# sensor_interface.net
KiCad netlist of a schematic drawn in EAGLE
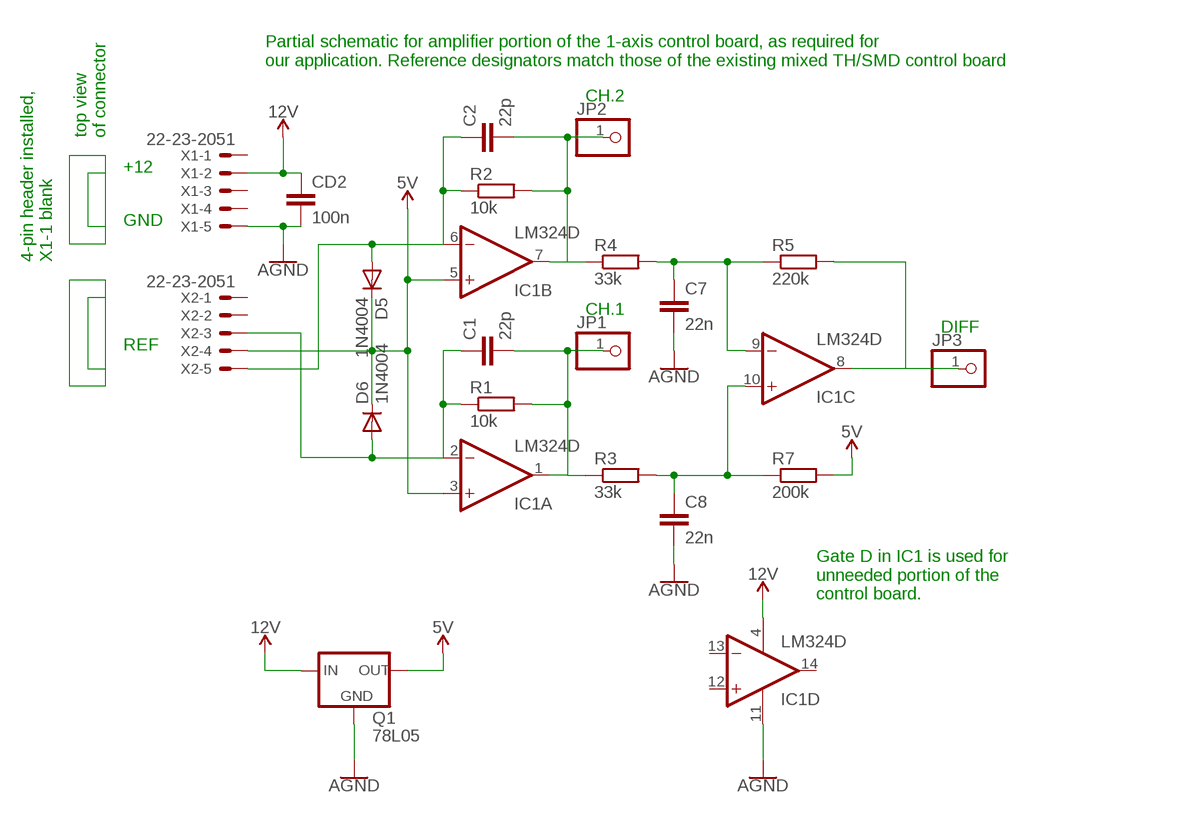
[diagram p0: schematic, sheet 1]

(export (version "E")
  (design (tool "Eeschema 10.0.6"))
  (components
    (comp (ref "C1")
      (value "22p")
      (footprint "eagle-import:C025-024X044")
      (libsource (lib "eagle-import") (part "C-EU025-024X044"))
    )
    (comp (ref "C2")
      (value "22p")
      (footprint "eagle-import:C025-024X044")
      (libsource (lib "eagle-import") (part "C-EU025-024X044"))
    )
    (comp (ref "C7")
      (value "22n")
      (footprint "eagle-import:C025-024X044")
      (libsource (lib "eagle-import") (part "C-EU025-024X044"))
    )
    (comp (ref "C8")
      (value "22n")
      (footprint "eagle-import:C025-024X044")
      (libsource (lib "eagle-import") (part "C-EU025-024X044"))
    )
    (comp (ref "CD2")
      (value "100n")
      (footprint "eagle-import:C025-024X044")
      (libsource (lib "eagle-import") (part "C-EU025-024X044"))
    )
    (comp (ref "D5")
      (value "1N4004")
      (footprint "eagle-import:DO41-10")
      (libsource (lib "eagle-import") (part "1N4004"))
    )
    (comp (ref "D6")
      (value "1N4004")
      (footprint "eagle-import:DO41-10")
      (libsource (lib "eagle-import") (part "1N4004"))
    )
    (comp (ref "IC1")
      (value "LM324D")
      (footprint "eagle-import:SO14")
      (libsource (lib "eagle-import") (part "LM324D"))
    )
    (comp (ref "JP1")
      (value "PINHD-1X1")
      (footprint "eagle-import:1X01")
      (libsource (lib "eagle-import") (part "PINHD-1X1"))
    )
    (comp (ref "JP2")
      (value "PINHD-1X1")
      (footprint "eagle-import:1X01")
      (libsource (lib "eagle-import") (part "PINHD-1X1"))
    )
    (comp (ref "JP3")
      (value "PINHD-1X1")
      (footprint "eagle-import:1X01")
      (libsource (lib "eagle-import") (part "PINHD-1X1"))
    )
    (comp (ref "Q1")
      (value "78L05")
      (footprint "eagle-import:78LXX")
      (libsource (lib "eagle-import") (part "78LXX"))
    )
    (comp (ref "R1")
      (value "10k")
      (footprint "eagle-import:R0805")
      (libsource (lib "eagle-import") (part "R-EU_R0805"))
    )
    (comp (ref "R2")
      (value "10k")
      (footprint "eagle-import:R0805")
      (libsource (lib "eagle-import") (part "R-EU_R0805"))
    )
    (comp (ref "R3")
      (value "33k")
      (footprint "eagle-import:R0805")
      (libsource (lib "eagle-import") (part "R-EU_R0805"))
    )
    (comp (ref "R4")
      (value "33k")
      (footprint "eagle-import:R0805")
      (libsource (lib "eagle-import") (part "R-EU_R0805"))
    )
    (comp (ref "R5")
      (value "220k")
      (footprint "eagle-import:R0805")
      (libsource (lib "eagle-import") (part "R-EU_R0805"))
    )
    (comp (ref "R7")
      (value "200k")
      (footprint "eagle-import:R0805")
      (libsource (lib "eagle-import") (part "R-EU_R0805"))
    )
    (comp (ref "X1")
      (value "22-23-2051")
      (footprint "eagle-import:22-23-2051")
      (fields (field (name "MF") "MOLEX"))
      (libsource (lib "eagle-import") (part "22-23-2051"))
    )
    (comp (ref "X2")
      (value "22-23-2051")
      (footprint "eagle-import:22-23-2051")
      (fields (field (name "MF") "MOLEX"))
      (libsource (lib "eagle-import") (part "22-23-2051"))
    )
  )
  (nets
    (net (code "1") (name "5V") (class "Default")
      (node (ref "D5") (pin "C") (pinfunction "C_C") (pintype "passive"))
      (node (ref "D6") (pin "C") (pinfunction "C_C") (pintype "passive"))
      (node (ref "IC1") (pin "3") (pinfunction "+IN_3") (pintype "input"))
      (node (ref "IC1") (pin "5") (pinfunction "+IN_5") (pintype "input"))
      (node (ref "Q1") (pin "OUT") (pinfunction "OUT_OUT") (pintype "passive"))
      (node (ref "R7") (pin "2") (pinfunction "2_2") (pintype "passive"))
      (node (ref "X2") (pin "4") (pinfunction "S_4") (pintype "passive"))
    )
    (net (code "2") (name "12V") (class "Default")
      (node (ref "CD2") (pin "1") (pinfunction "1_1") (pintype "passive"))
      (node (ref "IC1") (pin "4") (pinfunction "V+_4") (pintype "power_in"))
      (node (ref "Q1") (pin "IN") (pinfunction "IN_IN") (pintype "input"))
      (node (ref "X1") (pin "2") (pinfunction "S_2") (pintype "passive"))
    )
    (net (code "3") (name "AGND") (class "Default")
      (node (ref "C7") (pin "2") (pinfunction "2_2") (pintype "passive"))
      (node (ref "C8") (pin "2") (pinfunction "2_2") (pintype "passive"))
      (node (ref "CD2") (pin "2") (pinfunction "2_2") (pintype "passive"))
      (node (ref "IC1") (pin "11") (pinfunction "V-_11") (pintype "power_in"))
      (node (ref "Q1") (pin "GND") (pinfunction "GND_GND") (pintype "input"))
      (node (ref "X1") (pin "5") (pinfunction "S_5") (pintype "passive"))
    )
    (net (code "4") (name "Net-(IC1A--IN)") (class "Default")
      (node (ref "C1") (pin "1") (pinfunction "1_1") (pintype "passive"))
      (node (ref "D6") (pin "A") (pinfunction "A_A") (pintype "passive"))
      (node (ref "IC1") (pin "2") (pinfunction "-IN_2") (pintype "input"))
      (node (ref "R1") (pin "1") (pinfunction "1_1") (pintype "passive"))
      (node (ref "X2") (pin "3") (pinfunction "S_3") (pintype "passive"))
    )
    (net (code "5") (name "Net-(IC1A-OUT)") (class "Default")
      (node (ref "C1") (pin "2") (pinfunction "2_2") (pintype "passive"))
      (node (ref "IC1") (pin "1") (pinfunction "OUT_1") (pintype "output"))
      (node (ref "JP1") (pin "1") (pinfunction "1_1") (pintype "passive"))
      (node (ref "R1") (pin "2") (pinfunction "2_2") (pintype "passive"))
      (node (ref "R3") (pin "1") (pinfunction "1_1") (pintype "passive"))
    )
    (net (code "6") (name "Net-(IC1B--IN)") (class "Default")
      (node (ref "C2") (pin "1") (pinfunction "1_1") (pintype "passive"))
      (node (ref "D5") (pin "A") (pinfunction "A_A") (pintype "passive"))
      (node (ref "IC1") (pin "6") (pinfunction "-IN_6") (pintype "input"))
      (node (ref "R2") (pin "1") (pinfunction "1_1") (pintype "passive"))
      (node (ref "X2") (pin "5") (pinfunction "S_5") (pintype "passive"))
    )
    (net (code "7") (name "Net-(IC1B-OUT)") (class "Default")
      (node (ref "C2") (pin "2") (pinfunction "2_2") (pintype "passive"))
      (node (ref "IC1") (pin "7") (pinfunction "OUT_7") (pintype "output"))
      (node (ref "JP2") (pin "1") (pinfunction "1_1") (pintype "passive"))
      (node (ref "R2") (pin "2") (pinfunction "2_2") (pintype "passive"))
      (node (ref "R4") (pin "1") (pinfunction "1_1") (pintype "passive"))
    )
    (net (code "8") (name "Net-(IC1C-+IN)") (class "Default")
      (node (ref "C8") (pin "1") (pinfunction "1_1") (pintype "passive"))
      (node (ref "IC1") (pin "10") (pinfunction "+IN_10") (pintype "input"))
      (node (ref "R3") (pin "2") (pinfunction "2_2") (pintype "passive"))
      (node (ref "R7") (pin "1") (pinfunction "1_1") (pintype "passive"))
    )
    (net (code "9") (name "Net-(IC1C--IN)") (class "Default")
      (node (ref "C7") (pin "1") (pinfunction "1_1") (pintype "passive"))
      (node (ref "IC1") (pin "9") (pinfunction "-IN_9") (pintype "input"))
      (node (ref "R4") (pin "2") (pinfunction "2_2") (pintype "passive"))
      (node (ref "R5") (pin "1") (pinfunction "1_1") (pintype "passive"))
    )
    (net (code "10") (name "Net-(IC1C-OUT)") (class "Default")
      (node (ref "IC1") (pin "8") (pinfunction "OUT_8") (pintype "output"))
      (node (ref "JP3") (pin "1") (pinfunction "1_1") (pintype "passive"))
      (node (ref "R5") (pin "2") (pinfunction "2_2") (pintype "passive"))
    )
    (net (code "11") (name "unconnected-(IC1D-+IN-Pad12)") (class "Default")
      (node (ref "IC1") (pin "12") (pinfunction "+IN_12") (pintype "input"))
    )
    (net (code "12") (name "unconnected-(IC1D--IN-Pad13)") (class "Default")
      (node (ref "IC1") (pin "13") (pinfunction "-IN_13") (pintype "input"))
    )
    (net (code "13") (name "unconnected-(IC1D-OUT-Pad14)") (class "Default")
      (node (ref "IC1") (pin "14") (pinfunction "OUT_14") (pintype "output"))
    )
    (net (code "14") (name "unconnected-(X1A-S-Pad1)") (class "Default")
      (node (ref "X1") (pin "1") (pinfunction "S_1") (pintype "passive"))
    )
    (net (code "15") (name "unconnected-(X1C-S-Pad3)") (class "Default")
      (node (ref "X1") (pin "3") (pinfunction "S_3") (pintype "passive"))
    )
    (net (code "16") (name "unconnected-(X1D-S-Pad4)") (class "Default")
      (node (ref "X1") (pin "4") (pinfunction "S_4") (pintype "passive"))
    )
    (net (code "17") (name "unconnected-(X2A-S-Pad1)") (class "Default")
      (node (ref "X2") (pin "1") (pinfunction "S_1") (pintype "passive"))
    )
    (net (code "18") (name "unconnected-(X2B-S-Pad2)") (class "Default")
      (node (ref "X2") (pin "2") (pinfunction "S_2") (pintype "passive"))
    )
  )
)
